# pi-zigbee-poe-rtc.net
KiCad netlist of a schematic drawn in EAGLE
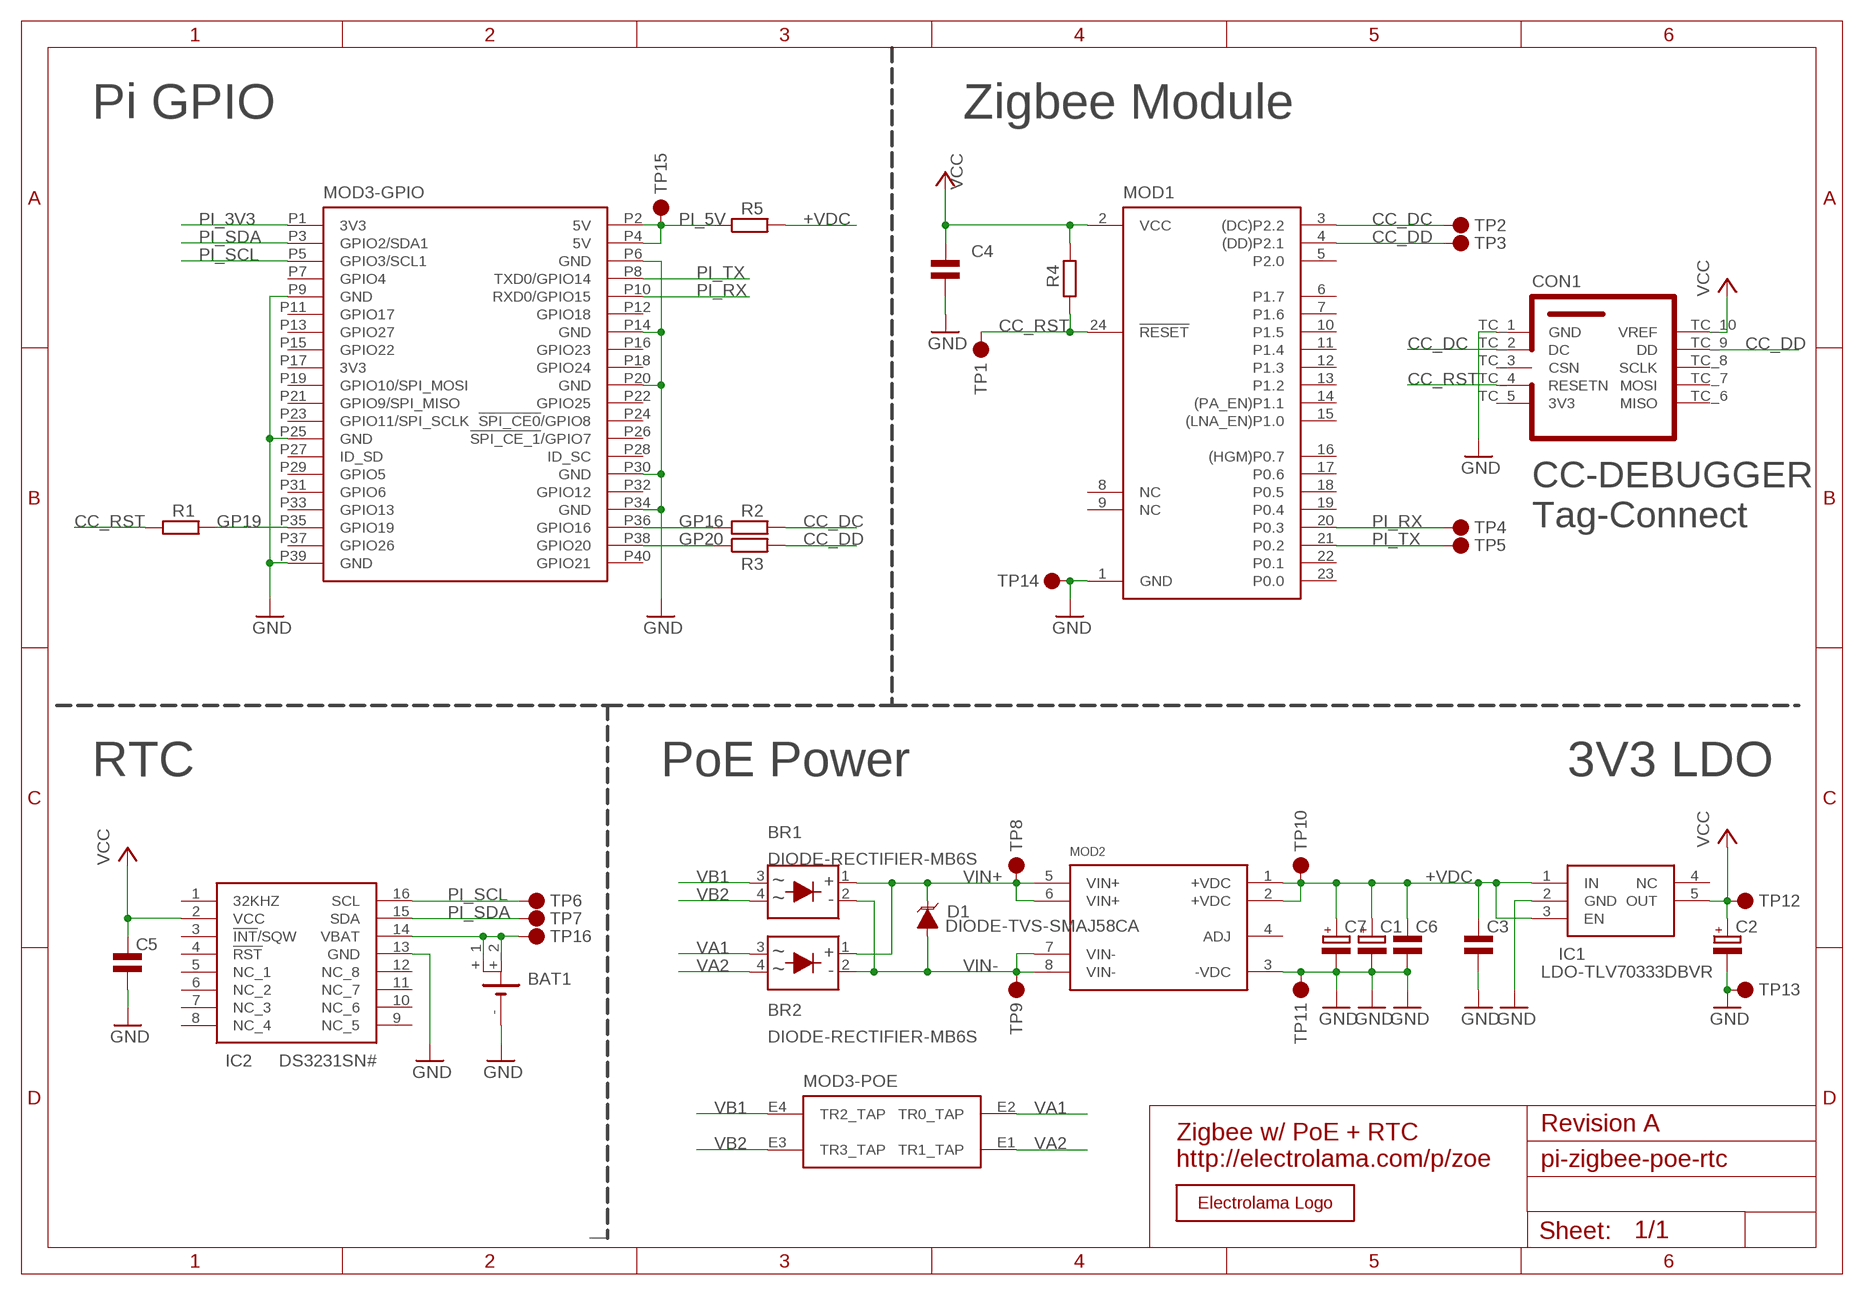
[diagram p0: schematic, sheet 1]

(export (version "E")
  (design (tool "Eeschema 10.0.6"))
  (components
    (comp (ref "BAT1")
      (value "BATTERY")
      (footprint "eagle-import:KEYSTONE_3001")
      (libsource (lib "eagle-import") (part "BATTERY"))
    )
    (comp (ref "BR1")
      (value "DIODE-RECTIFIER-MB6S")
      (footprint "eagle-import:SOP254P665X270-4N")
      (fields
        (field (name "MANUFACTURER_PART_NUMBER") "MB6S-TP")
        (field (name "MOUSER_PART_NUMBER") "833-MB6S-TP")
      )
      (libsource (lib "eagle-import") (part "DIODE-RECTIFIER-MB6S"))
    )
    (comp (ref "BR2")
      (value "DIODE-RECTIFIER-MB6S")
      (footprint "eagle-import:SOP254P665X270-4N")
      (fields
        (field (name "MANUFACTURER_PART_NUMBER") "MB6S-TP")
        (field (name "MOUSER_PART_NUMBER") "833-MB6S-TP")
      )
      (libsource (lib "eagle-import") (part "DIODE-RECTIFIER-MB6S"))
    )
    (comp (ref "C1")
      (value "CAP-POL-TANT-A")
      (footprint "eagle-import:_CAP_TANT_A_3216-18R")
      (libsource (lib "eagle-import") (part "CAP-POL-TANT-A"))
    )
    (comp (ref "C2")
      (value "CAP-POL-TANT-A")
      (footprint "eagle-import:_CAP_TANT_A_3216-18R")
      (libsource (lib "eagle-import") (part "CAP-POL-TANT-A"))
    )
    (comp (ref "C3")
      (value "CAP-0603")
      (footprint "eagle-import:_PKG_C_0603")
      (libsource (lib "eagle-import") (part "CAP-0603"))
    )
    (comp (ref "C4")
      (value "CAP-0603")
      (footprint "eagle-import:_PKG_C_0603")
      (libsource (lib "eagle-import") (part "CAP-0603"))
    )
    (comp (ref "C5")
      (value "CAP-0603")
      (footprint "eagle-import:_PKG_C_0603")
      (libsource (lib "eagle-import") (part "CAP-0603"))
    )
    (comp (ref "C6")
      (value "CAP-0603")
      (footprint "eagle-import:_PKG_C_0603")
      (libsource (lib "eagle-import") (part "CAP-0603"))
    )
    (comp (ref "C7")
      (value "CAP-POL-ELCO-D8-L10.5")
      (footprint "eagle-import:_CAP_ELCO_D8_L10.5")
      (libsource (lib "eagle-import") (part "CAP-POL-ELCO-D8-L10.5"))
    )
    (comp (ref "CON1")
      (value "TC2050-IDC-NL_CC-DEBUGGER")
      (footprint "eagle-import:TC2050-IDC-NL")
      (libsource (lib "eagle-import") (part "TC2050-IDC-NL_CC-DEBUGGER"))
    )
    (comp (ref "D1")
      (value "DIODE-TVS-SMAJ58CA")
      (footprint "eagle-import:DIOM5126X250N")
      (fields (field (name "MANUFACTURER_PART_NUMBER") "SMAJ58CA"))
      (libsource (lib "eagle-import") (part "DIODE-TVS-SMAJ58CA"))
    )
    (comp (ref "IC1")
      (value "LDO-TLV70333DBVR")
      (footprint "eagle-import:SOT95P280X145-5N")
      (fields
        (field (name "MANUFACTURER_PART_NUMBER") "TLV70333DBVR")
        (field (name "MOUSER_PART_NUMBER") "595-TLV70333DBVR")
      )
      (libsource (lib "eagle-import") (part "LDO-TLV70333DBVR"))
    )
    (comp (ref "IC2")
      (value "DS3231SN#")
      (footprint "eagle-import:SOIC127P1032X265-16N")
      (fields (field (name "MOUSER_PART_NUMBER") "700-DS3231SN#") (field (name "RS_PART_NUMBER") "1897251"))
      (libsource (lib "eagle-import") (part "DS3231SN#"))
    )
    (comp (ref "MOD1")
      (value "EBYTE-E18-MS1PA1")
      (footprint "eagle-import:EBYTE-E18-MS1PA1")
      (libsource (lib "eagle-import") (part "EBYTE-E18-MS1PA1"))
    )
    (comp (ref "MOD2")
      (value "SILVERTEL_AG9800M")
      (footprint "eagle-import:SILVERTEL_AG9800M")
      (libsource (lib "eagle-import") (part "SILVERTEL_AG9800M"))
    )
    (comp (ref "MOD3")
      (value "RPI-HAT-FULL")
      (footprint "eagle-import:RPI-HAT-FULL")
      (libsource (lib "eagle-import") (part "RPI-HAT-FULL"))
    )
    (comp (ref "R1")
      (value "RES-0603")
      (footprint "eagle-import:_PKG_C_0603")
      (libsource (lib "eagle-import") (part "RES-0603"))
    )
    (comp (ref "R2")
      (value "RES-0603")
      (footprint "eagle-import:_PKG_C_0603")
      (libsource (lib "eagle-import") (part "RES-0603"))
    )
    (comp (ref "R3")
      (value "RES-0603")
      (footprint "eagle-import:_PKG_C_0603")
      (libsource (lib "eagle-import") (part "RES-0603"))
    )
    (comp (ref "R4")
      (value "RES-0603")
      (footprint "eagle-import:_PKG_C_0603")
      (libsource (lib "eagle-import") (part "RES-0603"))
    )
    (comp (ref "R5")
      (value "RES-0603")
      (footprint "eagle-import:_PKG_C_0603")
      (libsource (lib "eagle-import") (part "RES-0603"))
    )
    (comp (ref "TP1") (value "TP") (footprint "eagle-import:TP") (libsource (lib "eagle-import") (part "TP")))
    (comp (ref "TP2") (value "TP") (footprint "eagle-import:TP") (libsource (lib "eagle-import") (part "TP")))
    (comp (ref "TP3") (value "TP") (footprint "eagle-import:TP") (libsource (lib "eagle-import") (part "TP")))
    (comp (ref "TP4") (value "TP") (footprint "eagle-import:TP") (libsource (lib "eagle-import") (part "TP")))
    (comp (ref "TP5") (value "TP") (footprint "eagle-import:TP") (libsource (lib "eagle-import") (part "TP")))
    (comp (ref "TP6") (value "TP") (footprint "eagle-import:TP") (libsource (lib "eagle-import") (part "TP")))
    (comp (ref "TP7") (value "TP") (footprint "eagle-import:TP") (libsource (lib "eagle-import") (part "TP")))
    (comp (ref "TP8") (value "TP") (footprint "eagle-import:TP") (libsource (lib "eagle-import") (part "TP")))
    (comp (ref "TP9") (value "TP") (footprint "eagle-import:TP") (libsource (lib "eagle-import") (part "TP")))
    (comp (ref "TP10")
      (value "TP")
      (footprint "eagle-import:TP")
      (libsource (lib "eagle-import") (part "TP"))
    )
    (comp (ref "TP11")
      (value "TP")
      (footprint "eagle-import:TP")
      (libsource (lib "eagle-import") (part "TP"))
    )
    (comp (ref "TP12")
      (value "TP")
      (footprint "eagle-import:TP")
      (libsource (lib "eagle-import") (part "TP"))
    )
    (comp (ref "TP13")
      (value "TP")
      (footprint "eagle-import:TP")
      (libsource (lib "eagle-import") (part "TP"))
    )
    (comp (ref "TP14")
      (value "TP")
      (footprint "eagle-import:TP")
      (libsource (lib "eagle-import") (part "TP"))
    )
    (comp (ref "TP15")
      (value "TP")
      (footprint "eagle-import:TP")
      (libsource (lib "eagle-import") (part "TP"))
    )
    (comp (ref "TP16")
      (value "TP")
      (footprint "eagle-import:TP")
      (libsource (lib "eagle-import") (part "TP"))
    )
    (comp (ref "U$1")
      (value "LOGO-ELECTROLAMA")
      (footprint "eagle-import:ELECTROLAMA")
      (libsource (lib "eagle-import") (part "LOGO-ELECTROLAMA"))
    )
  )
  (nets
    (net (code "1") (name "/+VDC") (class "Default")
      (node (ref "C1") (pin "+") (pinfunction "+_+") (pintype "passive"))
      (node (ref "C3") (pin "1") (pinfunction "1_1") (pintype "passive"))
      (node (ref "C6") (pin "1") (pinfunction "1_1") (pintype "passive"))
      (node (ref "C7") (pin "+") (pinfunction "+_+") (pintype "passive"))
      (node (ref "IC1") (pin "1") (pinfunction "IN_1") (pintype "bidirectional"))
      (node (ref "IC1") (pin "3") (pinfunction "EN_3") (pintype "bidirectional"))
      (node (ref "MOD2") (pin "1") (pinfunction "+VDC_1") (pintype "bidirectional"))
      (node (ref "MOD2") (pin "2") (pinfunction "+VDC_2") (pintype "bidirectional"))
      (node (ref "R5") (pin "2") (pinfunction "2_2") (pintype "passive"))
      (node (ref "TP10") (pin "TP") (pinfunction "TP_TP") (pintype "bidirectional"))
    )
    (net (code "2") (name "/CC_DC") (class "Default")
      (node (ref "CON1") (pin "TC_2") (pinfunction "DC_TC_2") (pintype "bidirectional"))
      (node (ref "MOD1") (pin "3") (pinfunction "(DC)P2.2_3") (pintype "bidirectional"))
      (node (ref "R2") (pin "2") (pinfunction "2_2") (pintype "passive"))
      (node (ref "TP2") (pin "TP") (pinfunction "TP_TP") (pintype "bidirectional"))
    )
    (net (code "3") (name "/CC_DD") (class "Default")
      (node (ref "CON1") (pin "TC_9") (pinfunction "DD_TC_9") (pintype "bidirectional"))
      (node (ref "MOD1") (pin "4") (pinfunction "(DD)P2.1_4") (pintype "bidirectional"))
      (node (ref "R3") (pin "2") (pinfunction "2_2") (pintype "passive"))
      (node (ref "TP3") (pin "TP") (pinfunction "TP_TP") (pintype "bidirectional"))
    )
    (net (code "4") (name "/CC_RST") (class "Default")
      (node (ref "CON1") (pin "TC_4") (pinfunction "RESETN_TC_4") (pintype "bidirectional"))
      (node (ref "MOD1") (pin "24") (pinfunction "~{RESET}_24") (pintype "input"))
      (node (ref "R1") (pin "1") (pinfunction "1_1") (pintype "passive"))
      (node (ref "R4") (pin "1") (pinfunction "1_1") (pintype "passive"))
      (node (ref "TP1") (pin "TP") (pinfunction "TP_TP") (pintype "bidirectional"))
    )
    (net (code "5") (name "/GP16") (class "Default")
      (node (ref "MOD3") (pin "P36") (pinfunction "GPIO16_P36") (pintype "bidirectional"))
      (node (ref "R2") (pin "1") (pinfunction "1_1") (pintype "passive"))
    )
    (net (code "6") (name "/GP19") (class "Default")
      (node (ref "MOD3") (pin "P35") (pinfunction "GPIO19_P35") (pintype "bidirectional"))
      (node (ref "R1") (pin "2") (pinfunction "2_2") (pintype "passive"))
    )
    (net (code "7") (name "/GP20") (class "Default")
      (node (ref "MOD3") (pin "P38") (pinfunction "GPIO20_P38") (pintype "bidirectional"))
      (node (ref "R3") (pin "1") (pinfunction "1_1") (pintype "passive"))
    )
    (net (code "8") (name "/PI_3V3") (class "Default")
      (node (ref "MOD3") (pin "P1") (pinfunction "3V3_P1") (pintype "bidirectional"))
    )
    (net (code "9") (name "/PI_5V") (class "Default")
      (node (ref "MOD3") (pin "P2") (pinfunction "5V_P2") (pintype "bidirectional"))
      (node (ref "MOD3") (pin "P4") (pinfunction "5V_P4") (pintype "bidirectional"))
      (node (ref "R5") (pin "1") (pinfunction "1_1") (pintype "passive"))
      (node (ref "TP15") (pin "TP") (pinfunction "TP_TP") (pintype "bidirectional"))
    )
    (net (code "10") (name "/PI_RX") (class "Default")
      (node (ref "MOD1") (pin "20") (pinfunction "P0.3_20") (pintype "bidirectional"))
      (node (ref "MOD3") (pin "P10") (pinfunction "RXD0/GPIO15_P10") (pintype "bidirectional"))
      (node (ref "TP4") (pin "TP") (pinfunction "TP_TP") (pintype "bidirectional"))
    )
    (net (code "11") (name "/PI_SCL") (class "Default")
      (node (ref "IC2") (pin "16") (pinfunction "SCL_16") (pintype "bidirectional"))
      (node (ref "MOD3") (pin "P5") (pinfunction "GPIO3/SCL1_P5") (pintype "bidirectional"))
      (node (ref "TP6") (pin "TP") (pinfunction "TP_TP") (pintype "bidirectional"))
    )
    (net (code "12") (name "/PI_SDA") (class "Default")
      (node (ref "IC2") (pin "15") (pinfunction "SDA_15") (pintype "bidirectional"))
      (node (ref "MOD3") (pin "P3") (pinfunction "GPIO2/SDA1_P3") (pintype "bidirectional"))
      (node (ref "TP7") (pin "TP") (pinfunction "TP_TP") (pintype "bidirectional"))
    )
    (net (code "13") (name "/PI_TX") (class "Default")
      (node (ref "MOD1") (pin "21") (pinfunction "P0.2_21") (pintype "bidirectional"))
      (node (ref "MOD3") (pin "P8") (pinfunction "TXD0/GPIO14_P8") (pintype "bidirectional"))
      (node (ref "TP5") (pin "TP") (pinfunction "TP_TP") (pintype "bidirectional"))
    )
    (net (code "14") (name "/VA1") (class "Default")
      (node (ref "BR2") (pin "3") (pinfunction "~_3") (pintype "bidirectional"))
      (node (ref "MOD3") (pin "E2") (pinfunction "TR0_TAP_E2") (pintype "bidirectional"))
    )
    (net (code "15") (name "/VA2") (class "Default")
      (node (ref "BR2") (pin "4") (pinfunction "~_4") (pintype "bidirectional"))
      (node (ref "MOD3") (pin "E1") (pinfunction "TR1_TAP_E1") (pintype "bidirectional"))
    )
    (net (code "16") (name "/VB1") (class "Default")
      (node (ref "BR1") (pin "3") (pinfunction "~_3") (pintype "bidirectional"))
      (node (ref "MOD3") (pin "E4") (pinfunction "TR2_TAP_E4") (pintype "bidirectional"))
    )
    (net (code "17") (name "/VB2") (class "Default")
      (node (ref "BR1") (pin "4") (pinfunction "~_4") (pintype "bidirectional"))
      (node (ref "MOD3") (pin "E3") (pinfunction "TR3_TAP_E3") (pintype "bidirectional"))
    )
    (net (code "18") (name "/VIN+") (class "Default")
      (node (ref "BR1") (pin "1") (pinfunction "+_1") (pintype "bidirectional"))
      (node (ref "BR2") (pin "1") (pinfunction "+_1") (pintype "bidirectional"))
      (node (ref "D1") (pin "1") (pinfunction "C_1") (pintype "passive"))
      (node (ref "MOD2") (pin "5") (pinfunction "VIN+_5") (pintype "bidirectional"))
      (node (ref "MOD2") (pin "6") (pinfunction "VIN+_6") (pintype "bidirectional"))
      (node (ref "TP8") (pin "TP") (pinfunction "TP_TP") (pintype "bidirectional"))
    )
    (net (code "19") (name "/VIN-") (class "Default")
      (node (ref "BR1") (pin "2") (pinfunction "-_2") (pintype "bidirectional"))
      (node (ref "BR2") (pin "2") (pinfunction "-_2") (pintype "bidirectional"))
      (node (ref "D1") (pin "2") (pinfunction "A_2") (pintype "passive"))
      (node (ref "MOD2") (pin "7") (pinfunction "VIN-_7") (pintype "bidirectional"))
      (node (ref "MOD2") (pin "8") (pinfunction "VIN-_8") (pintype "bidirectional"))
      (node (ref "TP9") (pin "TP") (pinfunction "TP_TP") (pintype "bidirectional"))
    )
    (net (code "20") (name "GND") (class "Default")
      (node (ref "BAT1") (pin "-") (pinfunction "-_-") (pintype "passive"))
      (node (ref "C1") (pin "-") (pinfunction "-_-") (pintype "passive"))
      (node (ref "C2") (pin "-") (pinfunction "-_-") (pintype "passive"))
      (node (ref "C3") (pin "2") (pinfunction "2_2") (pintype "passive"))
      (node (ref "C4") (pin "2") (pinfunction "2_2") (pintype "passive"))
      (node (ref "C5") (pin "2") (pinfunction "2_2") (pintype "passive"))
      (node (ref "C6") (pin "2") (pinfunction "2_2") (pintype "passive"))
      (node (ref "C7") (pin "-") (pinfunction "-_-") (pintype "passive"))
      (node (ref "CON1") (pin "TC_1") (pinfunction "GND_TC_1") (pintype "bidirectional"))
      (node (ref "IC1") (pin "2") (pinfunction "GND_2") (pintype "bidirectional"))
      (node (ref "IC2") (pin "13") (pinfunction "GND_13") (pintype "power_in"))
      (node (ref "MOD1") (pin "1") (pinfunction "GND_1") (pintype "power_in"))
      (node (ref "MOD2") (pin "3") (pinfunction "-VDC_3") (pintype "bidirectional"))
      (node (ref "MOD3") (pin "P14") (pinfunction "GND_P14") (pintype "bidirectional"))
      (node (ref "MOD3") (pin "P20") (pinfunction "GND_P20") (pintype "bidirectional"))
      (node (ref "MOD3") (pin "P25") (pinfunction "GND_P25") (pintype "bidirectional"))
      (node (ref "MOD3") (pin "P30") (pinfunction "GND_P30") (pintype "bidirectional"))
      (node (ref "MOD3") (pin "P34") (pinfunction "GND_P34") (pintype "bidirectional"))
      (node (ref "MOD3") (pin "P39") (pinfunction "GND_P39") (pintype "bidirectional"))
      (node (ref "MOD3") (pin "P6") (pinfunction "GND_P6") (pintype "bidirectional"))
      (node (ref "MOD3") (pin "P9") (pinfunction "GND_P9") (pintype "bidirectional"))
      (node (ref "TP11") (pin "TP") (pinfunction "TP_TP") (pintype "bidirectional"))
      (node (ref "TP13") (pin "TP") (pinfunction "TP_TP") (pintype "bidirectional"))
      (node (ref "TP14") (pin "TP") (pinfunction "TP_TP") (pintype "bidirectional"))
    )
    (net (code "21") (name "Net-(BAT1-+1)") (class "Default")
      (node (ref "BAT1") (pin "+_1") (pinfunction "+1_+_1") (pintype "passive"))
      (node (ref "BAT1") (pin "+_2") (pinfunction "+2_+_2") (pintype "passive"))
      (node (ref "IC2") (pin "14") (pinfunction "VBAT_14") (pintype "bidirectional"))
      (node (ref "TP16") (pin "TP") (pinfunction "TP_TP") (pintype "bidirectional"))
    )
    (net (code "22") (name "VCC") (class "Default")
      (node (ref "C2") (pin "+") (pinfunction "+_+") (pintype "passive"))
      (node (ref "C4") (pin "1") (pinfunction "1_1") (pintype "passive"))
      (node (ref "C5") (pin "1") (pinfunction "1_1") (pintype "passive"))
      (node (ref "CON1") (pin "TC_10") (pinfunction "VREF_TC_10") (pintype "bidirectional"))
      (node (ref "IC1") (pin "5") (pinfunction "OUT_5") (pintype "bidirectional"))
      (node (ref "IC2") (pin "2") (pinfunction "VCC_2") (pintype "power_in"))
      (node (ref "MOD1") (pin "2") (pinfunction "VCC_2") (pintype "power_in"))
      (node (ref "R4") (pin "2") (pinfunction "2_2") (pintype "passive"))
      (node (ref "TP12") (pin "TP") (pinfunction "TP_TP") (pintype "bidirectional"))
    )
    (net (code "23") (name "unconnected-(CON1-3V3-PadTC_5)") (class "Default")
      (node (ref "CON1") (pin "TC_5") (pinfunction "3V3_TC_5") (pintype "bidirectional"))
    )
    (net (code "24") (name "unconnected-(CON1-CSN-PadTC_3)") (class "Default")
      (node (ref "CON1") (pin "TC_3") (pinfunction "CSN_TC_3") (pintype "bidirectional"))
    )
    (net (code "25") (name "unconnected-(CON1-MISO-PadTC_6)") (class "Default")
      (node (ref "CON1") (pin "TC_6") (pinfunction "MISO_TC_6") (pintype "bidirectional"))
    )
    (net (code "26") (name "unconnected-(CON1-MOSI-PadTC_7)") (class "Default")
      (node (ref "CON1") (pin "TC_7") (pinfunction "MOSI_TC_7") (pintype "bidirectional"))
    )
    (net (code "27") (name "unconnected-(CON1-SCLK-PadTC_8)") (class "Default")
      (node (ref "CON1") (pin "TC_8") (pinfunction "SCLK_TC_8") (pintype "bidirectional"))
    )
    (net (code "28") (name "unconnected-(IC1-NC-Pad4)") (class "Default")
      (node (ref "IC1") (pin "4") (pinfunction "NC_4") (pintype "no_connect"))
    )
    (net (code "29") (name "unconnected-(IC2-32KHZ-Pad1)") (class "Default")
      (node (ref "IC2") (pin "1") (pinfunction "32KHZ_1") (pintype "bidirectional"))
    )
    (net (code "30") (name "unconnected-(IC2-NC_1-Pad5)") (class "Default")
      (node (ref "IC2") (pin "5") (pinfunction "NC_1_5") (pintype "bidirectional"))
    )
    (net (code "31") (name "unconnected-(IC2-NC_2-Pad6)") (class "Default")
      (node (ref "IC2") (pin "6") (pinfunction "NC_2_6") (pintype "bidirectional"))
    )
    (net (code "32") (name "unconnected-(IC2-NC_3-Pad7)") (class "Default")
      (node (ref "IC2") (pin "7") (pinfunction "NC_3_7") (pintype "bidirectional"))
    )
    (net (code "33") (name "unconnected-(IC2-NC_4-Pad8)") (class "Default")
      (node (ref "IC2") (pin "8") (pinfunction "NC_4_8") (pintype "bidirectional"))
    )
    (net (code "34") (name "unconnected-(IC2-NC_5-Pad9)") (class "Default")
      (node (ref "IC2") (pin "9") (pinfunction "NC_5_9") (pintype "bidirectional"))
    )
    (net (code "35") (name "unconnected-(IC2-NC_6-Pad10)") (class "Default")
      (node (ref "IC2") (pin "10") (pinfunction "NC_6_10") (pintype "bidirectional"))
    )
    (net (code "36") (name "unconnected-(IC2-NC_7-Pad11)") (class "Default")
      (node (ref "IC2") (pin "11") (pinfunction "NC_7_11") (pintype "bidirectional"))
    )
    (net (code "37") (name "unconnected-(IC2-NC_8-Pad12)") (class "Default")
      (node (ref "IC2") (pin "12") (pinfunction "NC_8_12") (pintype "bidirectional"))
    )
    (net (code "38") (name "unconnected-(IC2-~{INT}{slash}SQW-Pad3)") (class "Default")
      (node (ref "IC2") (pin "3") (pinfunction "~{INT}/SQW_3") (pintype "input"))
    )
    (net (code "39") (name "unconnected-(IC2-~{RST}-Pad4)") (class "Default")
      (node (ref "IC2") (pin "4") (pinfunction "~{RST}_4") (pintype "input"))
    )
    (net (code "40") (name "unconnected-(MOD1-(HGM)P0.7-Pad16)") (class "Default")
      (node (ref "MOD1") (pin "16") (pinfunction "(HGM)P0.7_16") (pintype "output"))
    )
    (net (code "41") (name "unconnected-(MOD1-(LNA_EN)P1.0-Pad15)") (class "Default")
      (node (ref "MOD1") (pin "15") (pinfunction "(LNA_EN)P1.0_15") (pintype "output"))
    )
    (net (code "42") (name "unconnected-(MOD1-(PA_EN)P1.1-Pad14)") (class "Default")
      (node (ref "MOD1") (pin "14") (pinfunction "(PA_EN)P1.1_14") (pintype "output"))
    )
    (net (code "43") (name "unconnected-(MOD1-NC-Pad8)") (class "Default")
      (node (ref "MOD1") (pin "8") (pinfunction "NC_8") (pintype "no_connect"))
    )
    (net (code "44") (name "unconnected-(MOD1-NC-Pad9)") (class "Default")
      (node (ref "MOD1") (pin "9") (pinfunction "NC_9") (pintype "no_connect"))
    )
    (net (code "45") (name "unconnected-(MOD1-P0.0-Pad23)") (class "Default")
      (node (ref "MOD1") (pin "23") (pinfunction "P0.0_23") (pintype "bidirectional"))
    )
    (net (code "46") (name "unconnected-(MOD1-P0.1-Pad22)") (class "Default")
      (node (ref "MOD1") (pin "22") (pinfunction "P0.1_22") (pintype "bidirectional"))
    )
    (net (code "47") (name "unconnected-(MOD1-P0.4-Pad19)") (class "Default")
      (node (ref "MOD1") (pin "19") (pinfunction "P0.4_19") (pintype "bidirectional"))
    )
    (net (code "48") (name "unconnected-(MOD1-P0.5-Pad18)") (class "Default")
      (node (ref "MOD1") (pin "18") (pinfunction "P0.5_18") (pintype "bidirectional"))
    )
    (net (code "49") (name "unconnected-(MOD1-P0.6-Pad17)") (class "Default")
      (node (ref "MOD1") (pin "17") (pinfunction "P0.6_17") (pintype "bidirectional"))
    )
    (net (code "50") (name "unconnected-(MOD1-P1.2-Pad13)") (class "Default")
      (node (ref "MOD1") (pin "13") (pinfunction "P1.2_13") (pintype "bidirectional"))
    )
    (net (code "51") (name "unconnected-(MOD1-P1.3-Pad12)") (class "Default")
      (node (ref "MOD1") (pin "12") (pinfunction "P1.3_12") (pintype "bidirectional"))
    )
    (net (code "52") (name "unconnected-(MOD1-P1.4-Pad11)") (class "Default")
      (node (ref "MOD1") (pin "11") (pinfunction "P1.4_11") (pintype "bidirectional"))
    )
    (net (code "53") (name "unconnected-(MOD1-P1.5-Pad10)") (class "Default")
      (node (ref "MOD1") (pin "10") (pinfunction "P1.5_10") (pintype "bidirectional"))
    )
    (net (code "54") (name "unconnected-(MOD1-P1.6-Pad7)") (class "Default")
      (node (ref "MOD1") (pin "7") (pinfunction "P1.6_7") (pintype "bidirectional"))
    )
    (net (code "55") (name "unconnected-(MOD1-P1.7-Pad6)") (class "Default")
      (node (ref "MOD1") (pin "6") (pinfunction "P1.7_6") (pintype "bidirectional"))
    )
    (net (code "56") (name "unconnected-(MOD1-P2.0-Pad5)") (class "Default")
      (node (ref "MOD1") (pin "5") (pinfunction "P2.0_5") (pintype "bidirectional"))
    )
    (net (code "57") (name "unconnected-(MOD2-ADJ-Pad4)") (class "Default")
      (node (ref "MOD2") (pin "4") (pinfunction "ADJ_4") (pintype "bidirectional"))
    )
    (net (code "58") (name "unconnected-(MOD3A-3V3-PadP17)") (class "Default")
      (node (ref "MOD3") (pin "P17") (pinfunction "3V3_P17") (pintype "bidirectional"))
    )
    (net (code "59") (name "unconnected-(MOD3A-GPIO4-PadP7)") (class "Default")
      (node (ref "MOD3") (pin "P7") (pinfunction "GPIO4_P7") (pintype "bidirectional"))
    )
    (net (code "60") (name "unconnected-(MOD3A-GPIO5-PadP29)") (class "Default")
      (node (ref "MOD3") (pin "P29") (pinfunction "GPIO5_P29") (pintype "bidirectional"))
    )
    (net (code "61") (name "unconnected-(MOD3A-GPIO6-PadP31)") (class "Default")
      (node (ref "MOD3") (pin "P31") (pinfunction "GPIO6_P31") (pintype "bidirectional"))
    )
    (net (code "62") (name "unconnected-(MOD3A-GPIO9{slash}SPI_MISO-PadP21)") (class "Default")
      (node (ref "MOD3") (pin "P21") (pinfunction "GPIO9/SPI_MISO_P21") (pintype "bidirectional"))
    )
    (net (code "63") (name "unconnected-(MOD3A-GPIO10{slash}SPI_MOSI-PadP19)") (class "Default")
      (node (ref "MOD3") (pin "P19") (pinfunction "GPIO10/SPI_MOSI_P19") (pintype "bidirectional"))
    )
    (net (code "64") (name "unconnected-(MOD3A-GPIO11{slash}SPI_SCLK-PadP23)") (class "Default")
      (node (ref "MOD3") (pin "P23") (pinfunction "GPIO11/SPI_SCLK_P23") (pintype "bidirectional"))
    )
    (net (code "65") (name "unconnected-(MOD3A-GPIO12-PadP32)") (class "Default")
      (node (ref "MOD3") (pin "P32") (pinfunction "GPIO12_P32") (pintype "bidirectional"))
    )
    (net (code "66") (name "unconnected-(MOD3A-GPIO13-PadP33)") (class "Default")
      (node (ref "MOD3") (pin "P33") (pinfunction "GPIO13_P33") (pintype "bidirectional"))
    )
    (net (code "67") (name "unconnected-(MOD3A-GPIO17-PadP11)") (class "Default")
      (node (ref "MOD3") (pin "P11") (pinfunction "GPIO17_P11") (pintype "bidirectional"))
    )
    (net (code "68") (name "unconnected-(MOD3A-GPIO18-PadP12)") (class "Default")
      (node (ref "MOD3") (pin "P12") (pinfunction "GPIO18_P12") (pintype "bidirectional"))
    )
    (net (code "69") (name "unconnected-(MOD3A-GPIO21-PadP40)") (class "Default")
      (node (ref "MOD3") (pin "P40") (pinfunction "GPIO21_P40") (pintype "bidirectional"))
    )
    (net (code "70") (name "unconnected-(MOD3A-GPIO22-PadP15)") (class "Default")
      (node (ref "MOD3") (pin "P15") (pinfunction "GPIO22_P15") (pintype "bidirectional"))
    )
    (net (code "71") (name "unconnected-(MOD3A-GPIO23-PadP16)") (class "Default")
      (node (ref "MOD3") (pin "P16") (pinfunction "GPIO23_P16") (pintype "bidirectional"))
    )
    (net (code "72") (name "unconnected-(MOD3A-GPIO24-PadP18)") (class "Default")
      (node (ref "MOD3") (pin "P18") (pinfunction "GPIO24_P18") (pintype "bidirectional"))
    )
    (net (code "73") (name "unconnected-(MOD3A-GPIO25-PadP22)") (class "Default")
      (node (ref "MOD3") (pin "P22") (pinfunction "GPIO25_P22") (pintype "bidirectional"))
    )
    (net (code "74") (name "unconnected-(MOD3A-GPIO26-PadP37)") (class "Default")
      (node (ref "MOD3") (pin "P37") (pinfunction "GPIO26_P37") (pintype "bidirectional"))
    )
    (net (code "75") (name "unconnected-(MOD3A-GPIO27-PadP13)") (class "Default")
      (node (ref "MOD3") (pin "P13") (pinfunction "GPIO27_P13") (pintype "bidirectional"))
    )
    (net (code "76") (name "unconnected-(MOD3A-ID_SC-PadP28)") (class "Default")
      (node (ref "MOD3") (pin "P28") (pinfunction "ID_SC_P28") (pintype "bidirectional"))
    )
    (net (code "77") (name "unconnected-(MOD3A-ID_SD-PadP27)") (class "Default")
      (node (ref "MOD3") (pin "P27") (pinfunction "ID_SD_P27") (pintype "bidirectional"))
    )
    (net (code "78") (name "unconnected-(MOD3A-~{SPI_CE0}{slash}GPIO8-PadP24)") (class "Default")
      (node (ref "MOD3") (pin "P24") (pinfunction "~{SPI_CE0}/GPIO8_P24") (pintype "bidirectional"))
    )
    (net (code "79") (name "unconnected-(MOD3A-~{SPI_CE_1}{slash}GPIO7-PadP26)") (class "Default")
      (node (ref "MOD3") (pin "P26") (pinfunction "~{SPI_CE_1}/GPIO7_P26") (pintype "bidirectional"))
    )
  )
)
